# E-29_Humidity_Sensor.net
KiCad netlist of a schematic drawn in Altium Designer
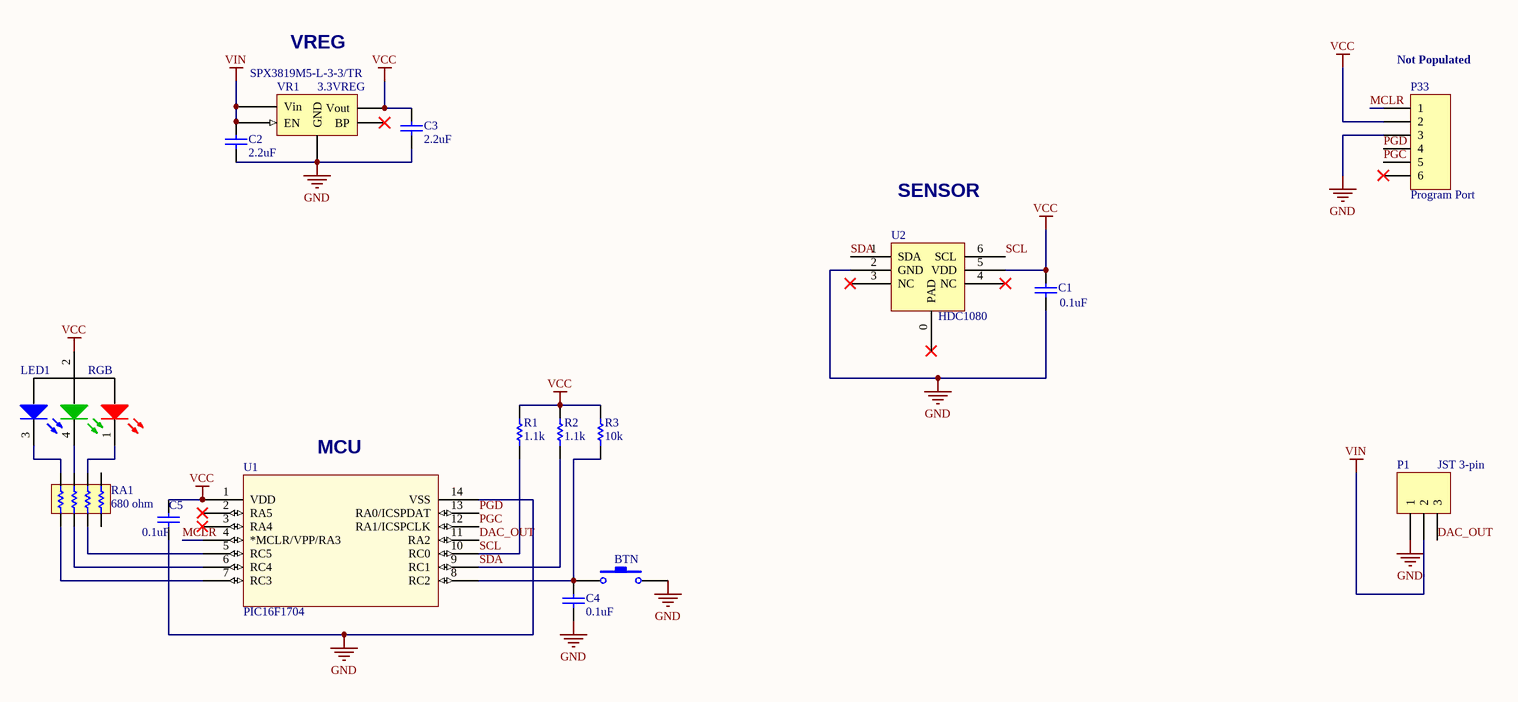
[diagram p0: E-29 Humidity Sensor.SchDoc]

(export (version "E")
  (design (tool "Eeschema 10.0.6"))
  (components
    (comp (ref "C1")
      (value "0.1uF")
      (footprint "0603 TIGHT")
      (description "Capacitor")
      (fields (field (name "Comment") "100nF") (field (name "PUBLISHER") "Altium Limited"))
      (libsource (lib "SB_Discrete") (part "Cap"))
    )
    (comp (ref "C2")
      (value "2.2uF")
      (footprint "0603 TIGHT")
      (description "Capacitor")
      (fields (field (name "PUBLISHER") "Altium Limited"))
      (libsource (lib "SB_Discrete") (part "Cap"))
    )
    (comp (ref "C3")
      (value "2.2uF")
      (footprint "0603 TIGHT")
      (description "Capacitor")
      (fields (field (name "Comment") "100nF") (field (name "PUBLISHER") "Altium Limited"))
      (libsource (lib "SB_Discrete") (part "Cap"))
    )
    (comp (ref "C4")
      (value "0.1uF")
      (footprint "0603 TIGHT")
      (description "Capacitor")
      (fields (field (name "Comment") "100nF") (field (name "PUBLISHER") "Altium Limited"))
      (libsource (lib "SB_Discrete") (part "Cap"))
    )
    (comp (ref "C5")
      (value "0.1uF")
      (footprint "0603 TIGHT")
      (description "Capacitor")
      (fields (field (name "Comment") "100nF") (field (name "PUBLISHER") "Altium Limited"))
      (libsource (lib "SB_Discrete") (part "Cap"))
    )
    (comp (ref "LED1")
      (value "RGB")
      (footprint "RGBLED-CA")
      (libsource (lib "SB_Discrete") (part "RGBLED-CA"))
    )
    (comp (ref "P1")
      (value "JST 3-pin")
      (footprint "JST-PH 3-pin SMD")
      (description "Header, 3-Pin")
      (fields (field (name "PUBLISHER") "Altium Limited"))
      (libsource (lib "Miscellaneous Connectors") (part "Header 3"))
    )
    (comp (ref "P33")
      (value "Program Port")
      (footprint "HDR1X6")
      (description "Header, 6-Pin")
      (fields (field (name "PUBLISHER") "Altium Limited"))
      (libsource (lib "Miscellaneous Connectors") (part "Header 6"))
    )
    (comp (ref "R1")
      (value "1.1k")
      (footprint "0603 TIGHT")
      (description "Resistor")
      (fields (field (name "Comment") "10kohm") (field (name "PUBLISHER") "Altium Limited"))
      (libsource (lib "SB_Discrete") (part "Res1"))
    )
    (comp (ref "R2")
      (value "1.1k")
      (footprint "0603 TIGHT")
      (description "Resistor")
      (fields (field (name "Comment") "10kohm") (field (name "PUBLISHER") "Altium Limited"))
      (libsource (lib "SB_Discrete") (part "Res1"))
    )
    (comp (ref "R3")
      (value "10k")
      (footprint "0603 TIGHT")
      (description "Resistor")
      (fields (field (name "Comment") "10kohm") (field (name "PUBLISHER") "Altium Limited"))
      (libsource (lib "SB_Discrete") (part "Res1"))
    )
    (comp (ref "RA1")
      (value "680 ohm")
      (footprint "Resistor Array 4")
      (libsource (lib "SB_Discrete") (part "Resistor Array 4"))
    )
    (comp (ref "S1") (value "BTN") (footprint "SW-SMD") (libsource (lib "SB_Discrete") (part "SW-SMD")))
    (comp (ref "U1")
      (value "PIC16F1704")
      (footprint "TSSOP14")
      (libsource (lib "SB_Engineered_Components") (part "PIC16F1704"))
    )
    (comp (ref "U2")
      (value "HDC1080")
      (footprint "HDC1080")
      (libsource (lib "SB_Engineered_Components") (part "HDC1080"))
    )
    (comp (ref "VR1")
      (value "3.3VREG")
      (footprint "SOT-25 New")
      (libsource (lib "SB_Discrete") (part "Vreg SOT25"))
    )
  )
  (nets
    (net (code "1") (name "/DAC_OUT") (class "Default")
      (node (ref "P1") (pin "3") (pinfunction "3_3") (pintype "passive"))
      (node (ref "U1") (pin "11") (pinfunction "RA2_11") (pintype "bidirectional"))
    )
    (net (code "2") (name "/MCLR") (class "Default")
      (node (ref "P33") (pin "1") (pinfunction "1_1") (pintype "passive"))
      (node (ref "U1") (pin "4") (pinfunction "*MCLR/VPP/RA3_4") (pintype "bidirectional"))
    )
    (net (code "3") (name "/PGC") (class "Default")
      (node (ref "P33") (pin "5") (pinfunction "5_5") (pintype "passive"))
      (node (ref "U1") (pin "12") (pinfunction "RA1/ICSPCLK_12") (pintype "bidirectional"))
    )
    (net (code "4") (name "/PGD") (class "Default")
      (node (ref "P33") (pin "4") (pinfunction "4_4") (pintype "passive"))
      (node (ref "U1") (pin "13") (pinfunction "RA0/ICSPDAT_13") (pintype "bidirectional"))
    )
    (net (code "5") (name "/SCL") (class "Default")
      (node (ref "R1") (pin "1") (pinfunction "1_1") (pintype "passive"))
      (node (ref "U1") (pin "10") (pinfunction "RC0_10") (pintype "bidirectional"))
      (node (ref "U2") (pin "6") (pinfunction "SCL_6") (pintype "passive"))
    )
    (net (code "6") (name "/SDA") (class "Default")
      (node (ref "R2") (pin "1") (pinfunction "1_1") (pintype "passive"))
      (node (ref "U1") (pin "9") (pinfunction "RC1_9") (pintype "bidirectional"))
      (node (ref "U2") (pin "1") (pinfunction "SDA_1") (pintype "passive"))
    )
    (net (code "8") (name "GND") (class "Default")
      (node (ref "C1") (pin "2") (pinfunction "2_2") (pintype "passive"))
      (node (ref "C2") (pin "2") (pinfunction "2_2") (pintype "passive"))
      (node (ref "C3") (pin "2") (pinfunction "2_2") (pintype "passive"))
      (node (ref "C4") (pin "2") (pinfunction "2_2") (pintype "passive"))
      (node (ref "C5") (pin "2") (pinfunction "2_2") (pintype "passive"))
      (node (ref "P1") (pin "1") (pinfunction "1_1") (pintype "passive"))
      (node (ref "P33") (pin "3") (pinfunction "3_3") (pintype "passive"))
      (node (ref "S1") (pin "2") (pinfunction "2_2") (pintype "passive"))
      (node (ref "U1") (pin "14") (pinfunction "VSS_14") (pintype "power_in"))
      (node (ref "U2") (pin "2") (pinfunction "GND_2") (pintype "passive"))
      (node (ref "VR1") (pin "3") (pinfunction "GND_3") (pintype "passive"))
    )
    (net (code "9") (name "Net-(LED1-Pad3)") (class "Default")
      (node (ref "LED1") (pin "3") (pinfunction "3_3") (pintype "passive"))
      (node (ref "RA1") (pin "2") (pinfunction "2_2") (pintype "passive"))
    )
    (net (code "10") (name "Net-(RA1-3)") (class "Default")
      (node (ref "RA1") (pin "5") (pinfunction "3_5") (pintype "passive"))
      (node (ref "U1") (pin "5") (pinfunction "RC5_5") (pintype "bidirectional"))
    )
    (net (code "11") (name "Net-(RA1-4)") (class "Default")
      (node (ref "LED1") (pin "1") (pinfunction "1_1") (pintype "passive"))
      (node (ref "RA1") (pin "6") (pinfunction "4_6") (pintype "passive"))
    )
    (net (code "12") (name "Net-(RA1-5)") (class "Default")
      (node (ref "RA1") (pin "3") (pinfunction "5_3") (pintype "passive"))
      (node (ref "U1") (pin "6") (pinfunction "RC4_6") (pintype "bidirectional"))
    )
    (net (code "13") (name "Net-(RA1-6)") (class "Default")
      (node (ref "LED1") (pin "4") (pinfunction "4_4") (pintype "passive"))
      (node (ref "RA1") (pin "4") (pinfunction "6_4") (pintype "passive"))
    )
    (net (code "14") (name "Net-(U1-RC2)") (class "Default")
      (node (ref "C4") (pin "1") (pinfunction "1_1") (pintype "passive"))
      (node (ref "R3") (pin "1") (pinfunction "1_1") (pintype "passive"))
      (node (ref "S1") (pin "1") (pinfunction "1_1") (pintype "passive"))
      (node (ref "U1") (pin "8") (pinfunction "RC2_8") (pintype "bidirectional"))
    )
    (net (code "15") (name "Net-(U1-RC3)") (class "Default")
      (node (ref "RA1") (pin "1") (pinfunction "1_1") (pintype "passive"))
      (node (ref "U1") (pin "7") (pinfunction "RC3_7") (pintype "bidirectional"))
    )
    (net (code "16") (name "VCC") (class "Default")
      (node (ref "C1") (pin "1") (pinfunction "1_1") (pintype "passive"))
      (node (ref "C3") (pin "1") (pinfunction "1_1") (pintype "passive"))
      (node (ref "C5") (pin "1") (pinfunction "1_1") (pintype "passive"))
      (node (ref "LED1") (pin "2") (pinfunction "2_2") (pintype "passive"))
      (node (ref "P33") (pin "2") (pinfunction "2_2") (pintype "passive"))
      (node (ref "R1") (pin "2") (pinfunction "2_2") (pintype "passive"))
      (node (ref "R2") (pin "2") (pinfunction "2_2") (pintype "passive"))
      (node (ref "R3") (pin "2") (pinfunction "2_2") (pintype "passive"))
      (node (ref "U1") (pin "1") (pinfunction "VDD_1") (pintype "power_in"))
      (node (ref "U2") (pin "5") (pinfunction "VDD_5") (pintype "passive"))
      (node (ref "VR1") (pin "2") (pinfunction "Vout_2") (pintype "passive"))
    )
    (net (code "17") (name "VIN") (class "Default")
      (node (ref "C2") (pin "1") (pinfunction "1_1") (pintype "passive"))
      (node (ref "P1") (pin "2") (pinfunction "2_2") (pintype "passive"))
      (node (ref "VR1") (pin "4") (pinfunction "EN_4") (pintype "input"))
      (node (ref "VR1") (pin "5") (pinfunction "Vin_5") (pintype "passive"))
    )
    (net (code "18") (name "unconnected-(P33-Pad6)") (class "Default")
      (node (ref "P33") (pin "6") (pinfunction "6_6") (pintype "passive+no_connect"))
    )
    (net (code "19") (name "unconnected-(RA1-Pad7)") (class "Default")
      (node (ref "RA1") (pin "7") (pinfunction "7_7") (pintype "passive"))
    )
    (net (code "20") (name "unconnected-(RA1-Pad8)") (class "Default")
      (node (ref "RA1") (pin "8") (pinfunction "8_8") (pintype "passive"))
    )
    (net (code "21") (name "unconnected-(U1-RA4-Pad3)") (class "Default")
      (node (ref "U1") (pin "3") (pinfunction "RA4_3") (pintype "bidirectional+no_connect"))
    )
    (net (code "22") (name "unconnected-(U1-RA5-Pad2)") (class "Default")
      (node (ref "U1") (pin "2") (pinfunction "RA5_2") (pintype "bidirectional+no_connect"))
    )
    (net (code "23") (name "unconnected-(U2-NC-Pad3)") (class "Default")
      (node (ref "U2") (pin "3") (pinfunction "NC_3") (pintype "passive+no_connect"))
    )
    (net (code "24") (name "unconnected-(U2-NC-Pad4)") (class "Default")
      (node (ref "U2") (pin "4") (pinfunction "NC_4") (pintype "passive+no_connect"))
    )
    (net (code "25") (name "unconnected-(U2-PAD-Pad0)") (class "Default")
      (node (ref "U2") (pin "0") (pinfunction "PAD_0") (pintype "passive+no_connect"))
    )
    (net (code "26") (name "unconnected-(VR1-BP-Pad1)") (class "Default")
      (node (ref "VR1") (pin "1") (pinfunction "BP_1") (pintype "passive+no_connect"))
    )
  )
)
